# Shunt_Regulator.net
KiCad netlist of a schematic drawn in EAGLE
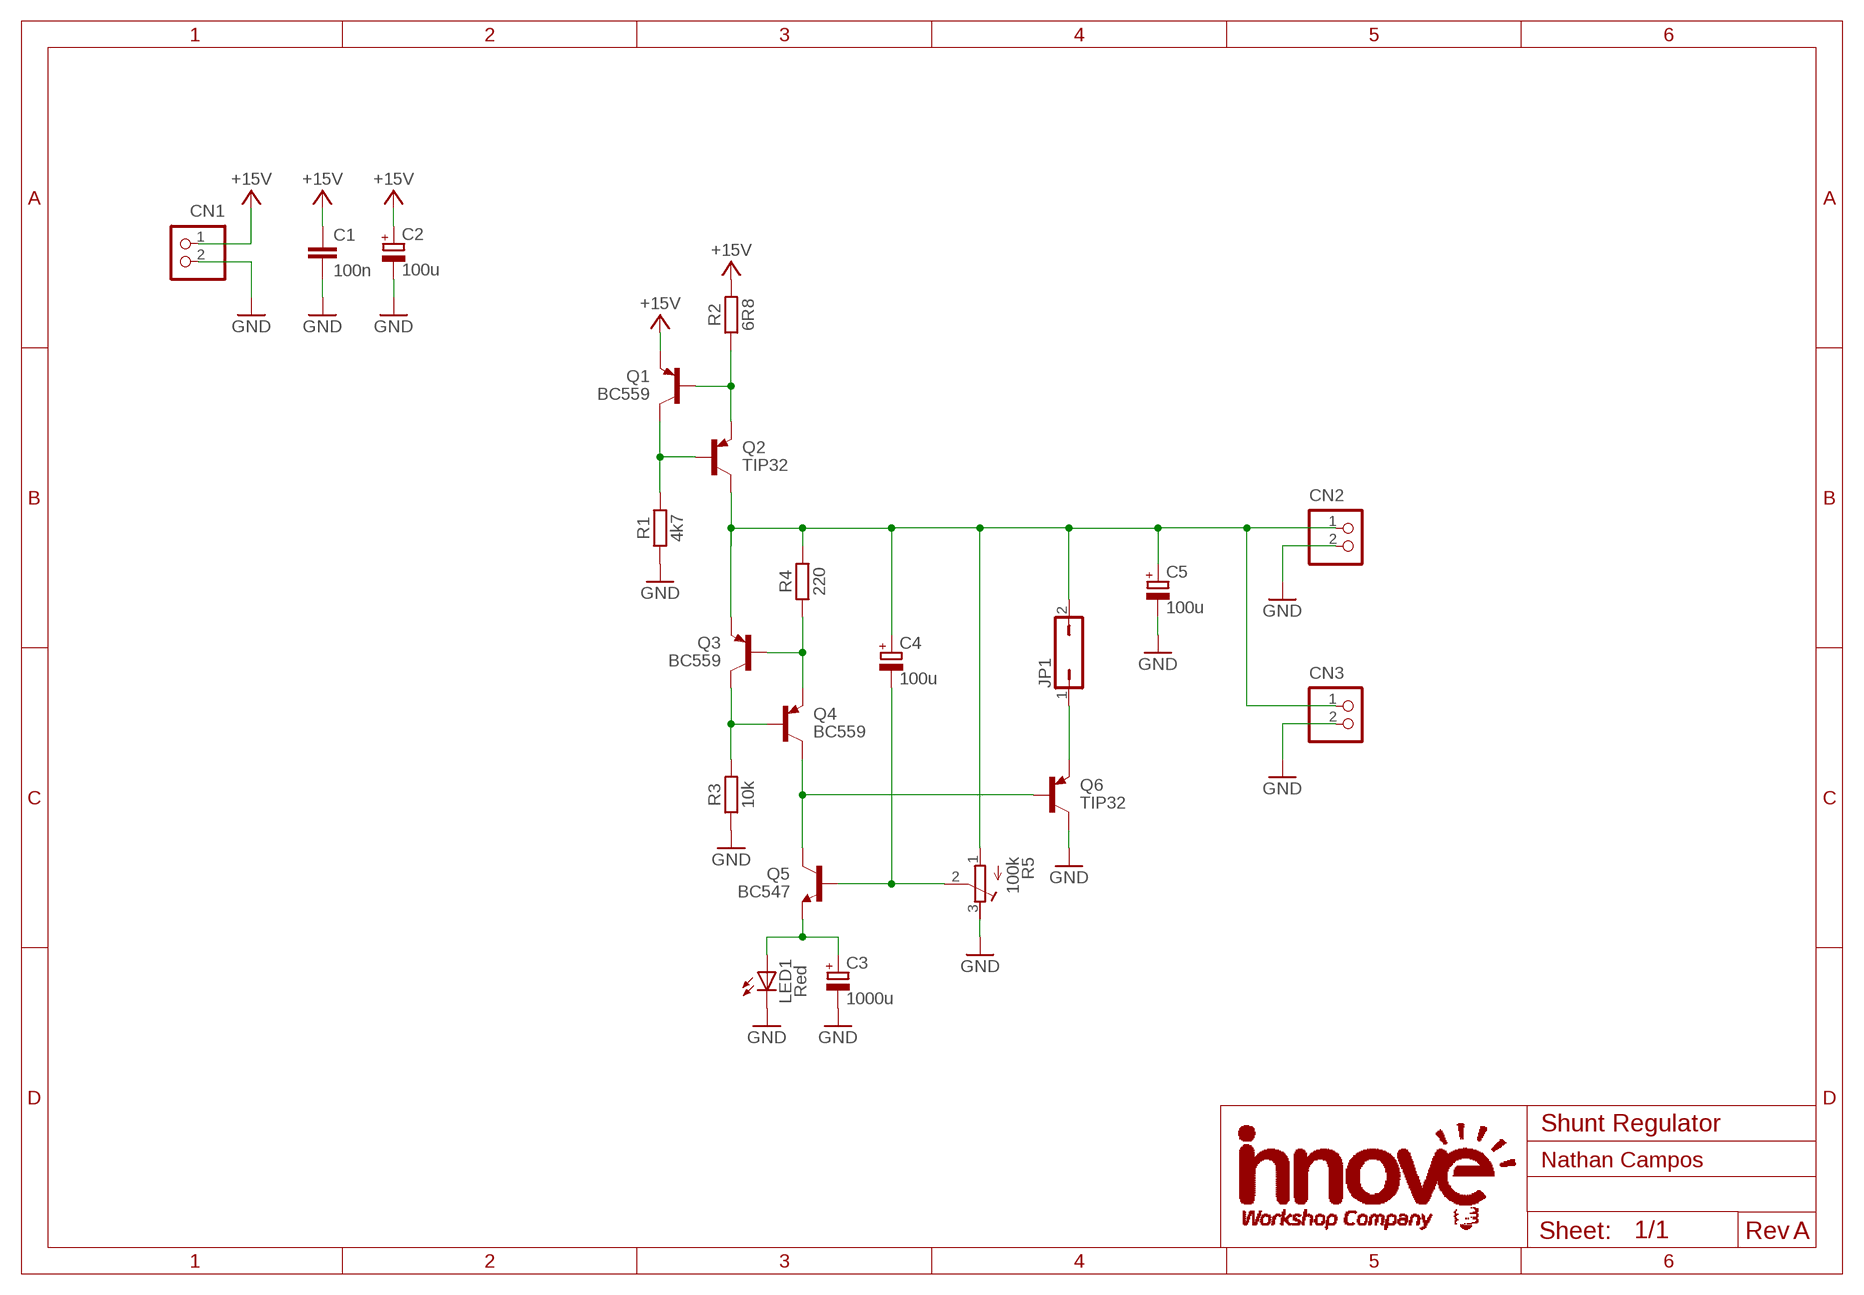
[diagram p0: schematic, sheet 1]

(export (version "E")
  (design (tool "Eeschema 10.0.6"))
  (components
    (comp (ref "C1")
      (value "100n")
      (footprint "eagle-import:C050-025X075")
      (libsource (lib "eagle-import") (part "C5.0-2.5X7.5"))
    )
    (comp (ref "C2")
      (value "100u")
      (footprint "eagle-import:E2,5-6")
      (libsource (lib "eagle-import") (part "CPOL-E2.5-6"))
    )
    (comp (ref "C3")
      (value "1000u")
      (footprint "eagle-import:E5-10")
      (libsource (lib "eagle-import") (part "CPOL-E5-10"))
    )
    (comp (ref "C4")
      (value "100u")
      (footprint "eagle-import:E2,5-6")
      (libsource (lib "eagle-import") (part "CPOL-E2.5-6"))
    )
    (comp (ref "C5")
      (value "100u")
      (footprint "eagle-import:E2,5-6")
      (libsource (lib "eagle-import") (part "CPOL-E2.5-6"))
    )
    (comp (ref "CN1")
      (value "B2B-XH-A")
      (footprint "eagle-import:B2B-XH-A")
      (libsource (lib "eagle-import") (part "B2B-XH-A"))
    )
    (comp (ref "CN2")
      (value "B2B-XH-A")
      (footprint "eagle-import:B2B-XH-A")
      (libsource (lib "eagle-import") (part "B2B-XH-A"))
    )
    (comp (ref "CN3")
      (value "B2B-XH-A")
      (footprint "eagle-import:B2B-XH-A")
      (libsource (lib "eagle-import") (part "B2B-XH-A"))
    )
    (comp (ref "JP1")
      (value "JP1Q")
      (footprint "eagle-import:JP1")
      (libsource (lib "eagle-import") (part "JP1Q"))
    )
    (comp (ref "LED1")
      (value "Red")
      (footprint "eagle-import:LED5MM")
      (libsource (lib "eagle-import") (part "LED5MM"))
    )
    (comp (ref "Q1")
      (value "BC559")
      (footprint "eagle-import:TO92")
      (libsource (lib "eagle-import") (part "BC559"))
    )
    (comp (ref "Q2")
      (value "TIP32")
      (footprint "eagle-import:TO220V")
      (libsource (lib "eagle-import") (part "TIP32"))
    )
    (comp (ref "Q3")
      (value "BC559")
      (footprint "eagle-import:TO92")
      (libsource (lib "eagle-import") (part "BC559"))
    )
    (comp (ref "Q4")
      (value "BC559")
      (footprint "eagle-import:TO92")
      (libsource (lib "eagle-import") (part "BC559"))
    )
    (comp (ref "Q5")
      (value "BC547")
      (footprint "eagle-import:TO92")
      (libsource (lib "eagle-import") (part "BC547"))
    )
    (comp (ref "Q6")
      (value "TIP32")
      (footprint "eagle-import:TO220V")
      (libsource (lib "eagle-import") (part "TIP32"))
    )
    (comp (ref "R1")
      (value "4k7")
      (footprint "eagle-import:0207_10")
      (libsource (lib "eagle-import") (part "RT0207"))
    )
    (comp (ref "R2")
      (value "6R8")
      (footprint "eagle-import:0207_10")
      (libsource (lib "eagle-import") (part "RT0207"))
    )
    (comp (ref "R3")
      (value "10k")
      (footprint "eagle-import:0207_10")
      (libsource (lib "eagle-import") (part "RT0207"))
    )
    (comp (ref "R4")
      (value "220")
      (footprint "eagle-import:0207_10")
      (libsource (lib "eagle-import") (part "RT0207"))
    )
    (comp (ref "R5")
      (value "100k")
      (footprint "eagle-import:RTRIM3296Y")
      (libsource (lib "eagle-import") (part "R-TRIMM3296Y"))
    )
  )
  (nets
    (net (code "1") (name "+15V") (class "Default")
      (node (ref "C1") (pin "1") (pinfunction "1_1") (pintype "passive"))
      (node (ref "C2") (pin "+") (pinfunction "+_+") (pintype "passive"))
      (node (ref "CN1") (pin "1") (pinfunction "1_1") (pintype "passive"))
      (node (ref "Q1") (pin "3") (pinfunction "E_3") (pintype "passive"))
      (node (ref "R2") (pin "2") (pinfunction "2_2") (pintype "passive"))
    )
    (net (code "2") (name "GND") (class "Default")
      (node (ref "C1") (pin "2") (pinfunction "2_2") (pintype "passive"))
      (node (ref "C2") (pin "-") (pinfunction "-_-") (pintype "passive"))
      (node (ref "C3") (pin "-") (pinfunction "-_-") (pintype "passive"))
      (node (ref "C5") (pin "-") (pinfunction "-_-") (pintype "passive"))
      (node (ref "CN1") (pin "2") (pinfunction "2_2") (pintype "passive"))
      (node (ref "CN2") (pin "2") (pinfunction "2_2") (pintype "passive"))
      (node (ref "CN3") (pin "2") (pinfunction "2_2") (pintype "passive"))
      (node (ref "LED1") (pin "K") (pinfunction "C_K") (pintype "passive"))
      (node (ref "Q6") (pin "2") (pinfunction "C_2") (pintype "passive"))
      (node (ref "R1") (pin "1") (pinfunction "1_1") (pintype "passive"))
      (node (ref "R3") (pin "1") (pinfunction "1_1") (pintype "passive"))
      (node (ref "R5") (pin "3") (pinfunction "E_3") (pintype "passive"))
    )
    (net (code "3") (name "Net-(Q1-B)") (class "Default")
      (node (ref "Q1") (pin "2") (pinfunction "B_2") (pintype "passive"))
      (node (ref "Q2") (pin "3") (pinfunction "E_3") (pintype "passive"))
      (node (ref "R2") (pin "1") (pinfunction "1_1") (pintype "passive"))
    )
    (net (code "4") (name "Net-(Q1-C)") (class "Default")
      (node (ref "Q1") (pin "1") (pinfunction "C_1") (pintype "passive"))
      (node (ref "Q2") (pin "1") (pinfunction "B_1") (pintype "passive"))
      (node (ref "R1") (pin "2") (pinfunction "2_2") (pintype "passive"))
    )
    (net (code "5") (name "Net-(Q2-C)") (class "Default")
      (node (ref "C4") (pin "+") (pinfunction "+_+") (pintype "passive"))
      (node (ref "C5") (pin "+") (pinfunction "+_+") (pintype "passive"))
      (node (ref "CN2") (pin "1") (pinfunction "1_1") (pintype "passive"))
      (node (ref "CN3") (pin "1") (pinfunction "1_1") (pintype "passive"))
      (node (ref "JP1") (pin "2") (pinfunction "2_2") (pintype "passive"))
      (node (ref "Q2") (pin "2") (pinfunction "C_2") (pintype "passive"))
      (node (ref "Q3") (pin "3") (pinfunction "E_3") (pintype "passive"))
      (node (ref "R4") (pin "2") (pinfunction "2_2") (pintype "passive"))
      (node (ref "R5") (pin "1") (pinfunction "A_1") (pintype "passive"))
    )
    (net (code "6") (name "Net-(Q3-B)") (class "Default")
      (node (ref "Q3") (pin "2") (pinfunction "B_2") (pintype "passive"))
      (node (ref "Q4") (pin "3") (pinfunction "E_3") (pintype "passive"))
      (node (ref "R4") (pin "1") (pinfunction "1_1") (pintype "passive"))
    )
    (net (code "7") (name "Net-(Q3-C)") (class "Default")
      (node (ref "Q3") (pin "1") (pinfunction "C_1") (pintype "passive"))
      (node (ref "Q4") (pin "2") (pinfunction "B_2") (pintype "passive"))
      (node (ref "R3") (pin "2") (pinfunction "2_2") (pintype "passive"))
    )
    (net (code "8") (name "Net-(Q4-C)") (class "Default")
      (node (ref "Q4") (pin "1") (pinfunction "C_1") (pintype "passive"))
      (node (ref "Q5") (pin "1") (pinfunction "C_1") (pintype "passive"))
      (node (ref "Q6") (pin "1") (pinfunction "B_1") (pintype "passive"))
    )
    (net (code "9") (name "Net-(Q5-B)") (class "Default")
      (node (ref "C4") (pin "-") (pinfunction "-_-") (pintype "passive"))
      (node (ref "Q5") (pin "2") (pinfunction "B_2") (pintype "passive"))
      (node (ref "R5") (pin "2") (pinfunction "S_2") (pintype "passive"))
    )
    (net (code "10") (name "Net-(Q5-E)") (class "Default")
      (node (ref "C3") (pin "+") (pinfunction "+_+") (pintype "passive"))
      (node (ref "LED1") (pin "A") (pinfunction "A_A") (pintype "passive"))
      (node (ref "Q5") (pin "3") (pinfunction "E_3") (pintype "passive"))
    )
    (net (code "11") (name "Net-(Q6-E)") (class "Default")
      (node (ref "JP1") (pin "1") (pinfunction "1_1") (pintype "passive"))
      (node (ref "Q6") (pin "3") (pinfunction "E_3") (pintype "passive"))
    )
  )
)
